# SXLP-450.net
KiCad netlist of a schematic drawn in Altium Designer
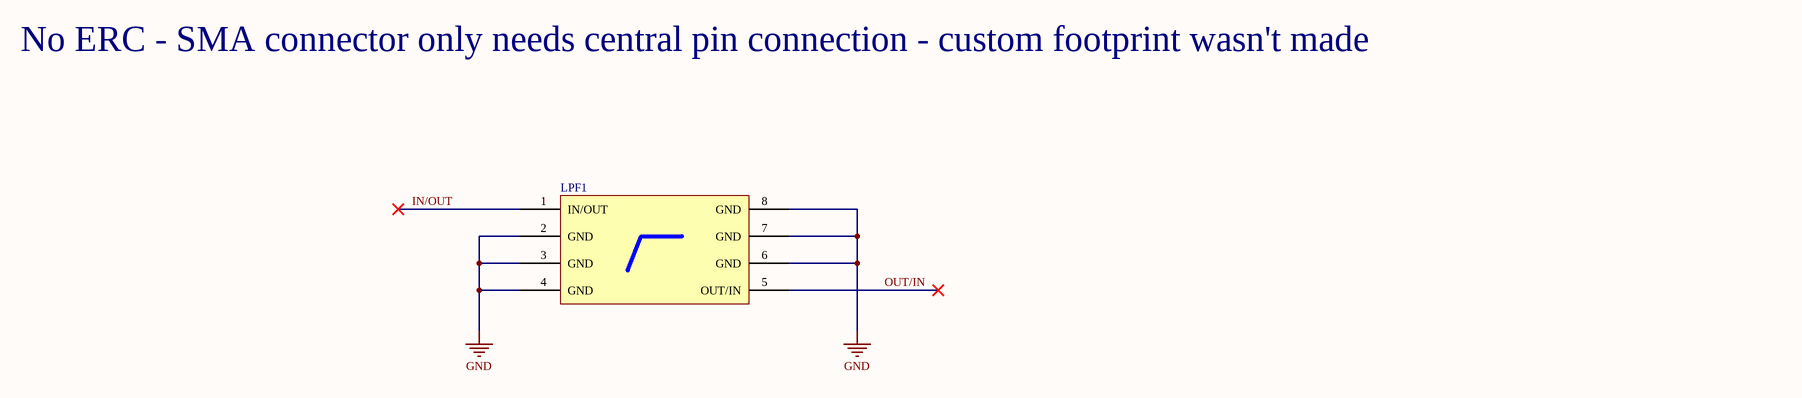
[diagram p0: SXLP-450+.SchDoc]

(export (version "E")
  (design (tool "Eeschema 10.0.6"))
  (components
    (comp (ref "LPF1")
      (value "~")
      (footprint "SXLP-450+")
      (description "SXLP-450+, Low Pass Filter, Mini Circuits, DC to 450 MHz")
      (libsource (lib "SXLP-450+") (part "SXLP-450+"))
    )
  )
  (nets
    (net (code "1") (name "/IN{slash}OUT") (class "Default")
      (node (ref "LPF1") (pin "1") (pinfunction "IN/OUT_1") (pintype "passive+no_connect"))
    )
    (net (code "2") (name "/OUT{slash}IN") (class "Default")
      (node (ref "LPF1") (pin "5") (pinfunction "OUT/IN_5") (pintype "passive+no_connect"))
    )
    (net (code "3") (name "GND") (class "Default")
      (node (ref "LPF1") (pin "2") (pinfunction "GND_2") (pintype "passive"))
      (node (ref "LPF1") (pin "3") (pinfunction "GND_3") (pintype "passive"))
      (node (ref "LPF1") (pin "4") (pinfunction "GND_4") (pintype "passive"))
      (node (ref "LPF1") (pin "6") (pinfunction "GND_6") (pintype "passive"))
      (node (ref "LPF1") (pin "7") (pinfunction "GND_7") (pintype "passive"))
      (node (ref "LPF1") (pin "8") (pinfunction "GND_8") (pintype "passive"))
    )
  )
)
